# 1-Schematic_TL071.net
KiCad netlist of a schematic drawn in EasyEDA
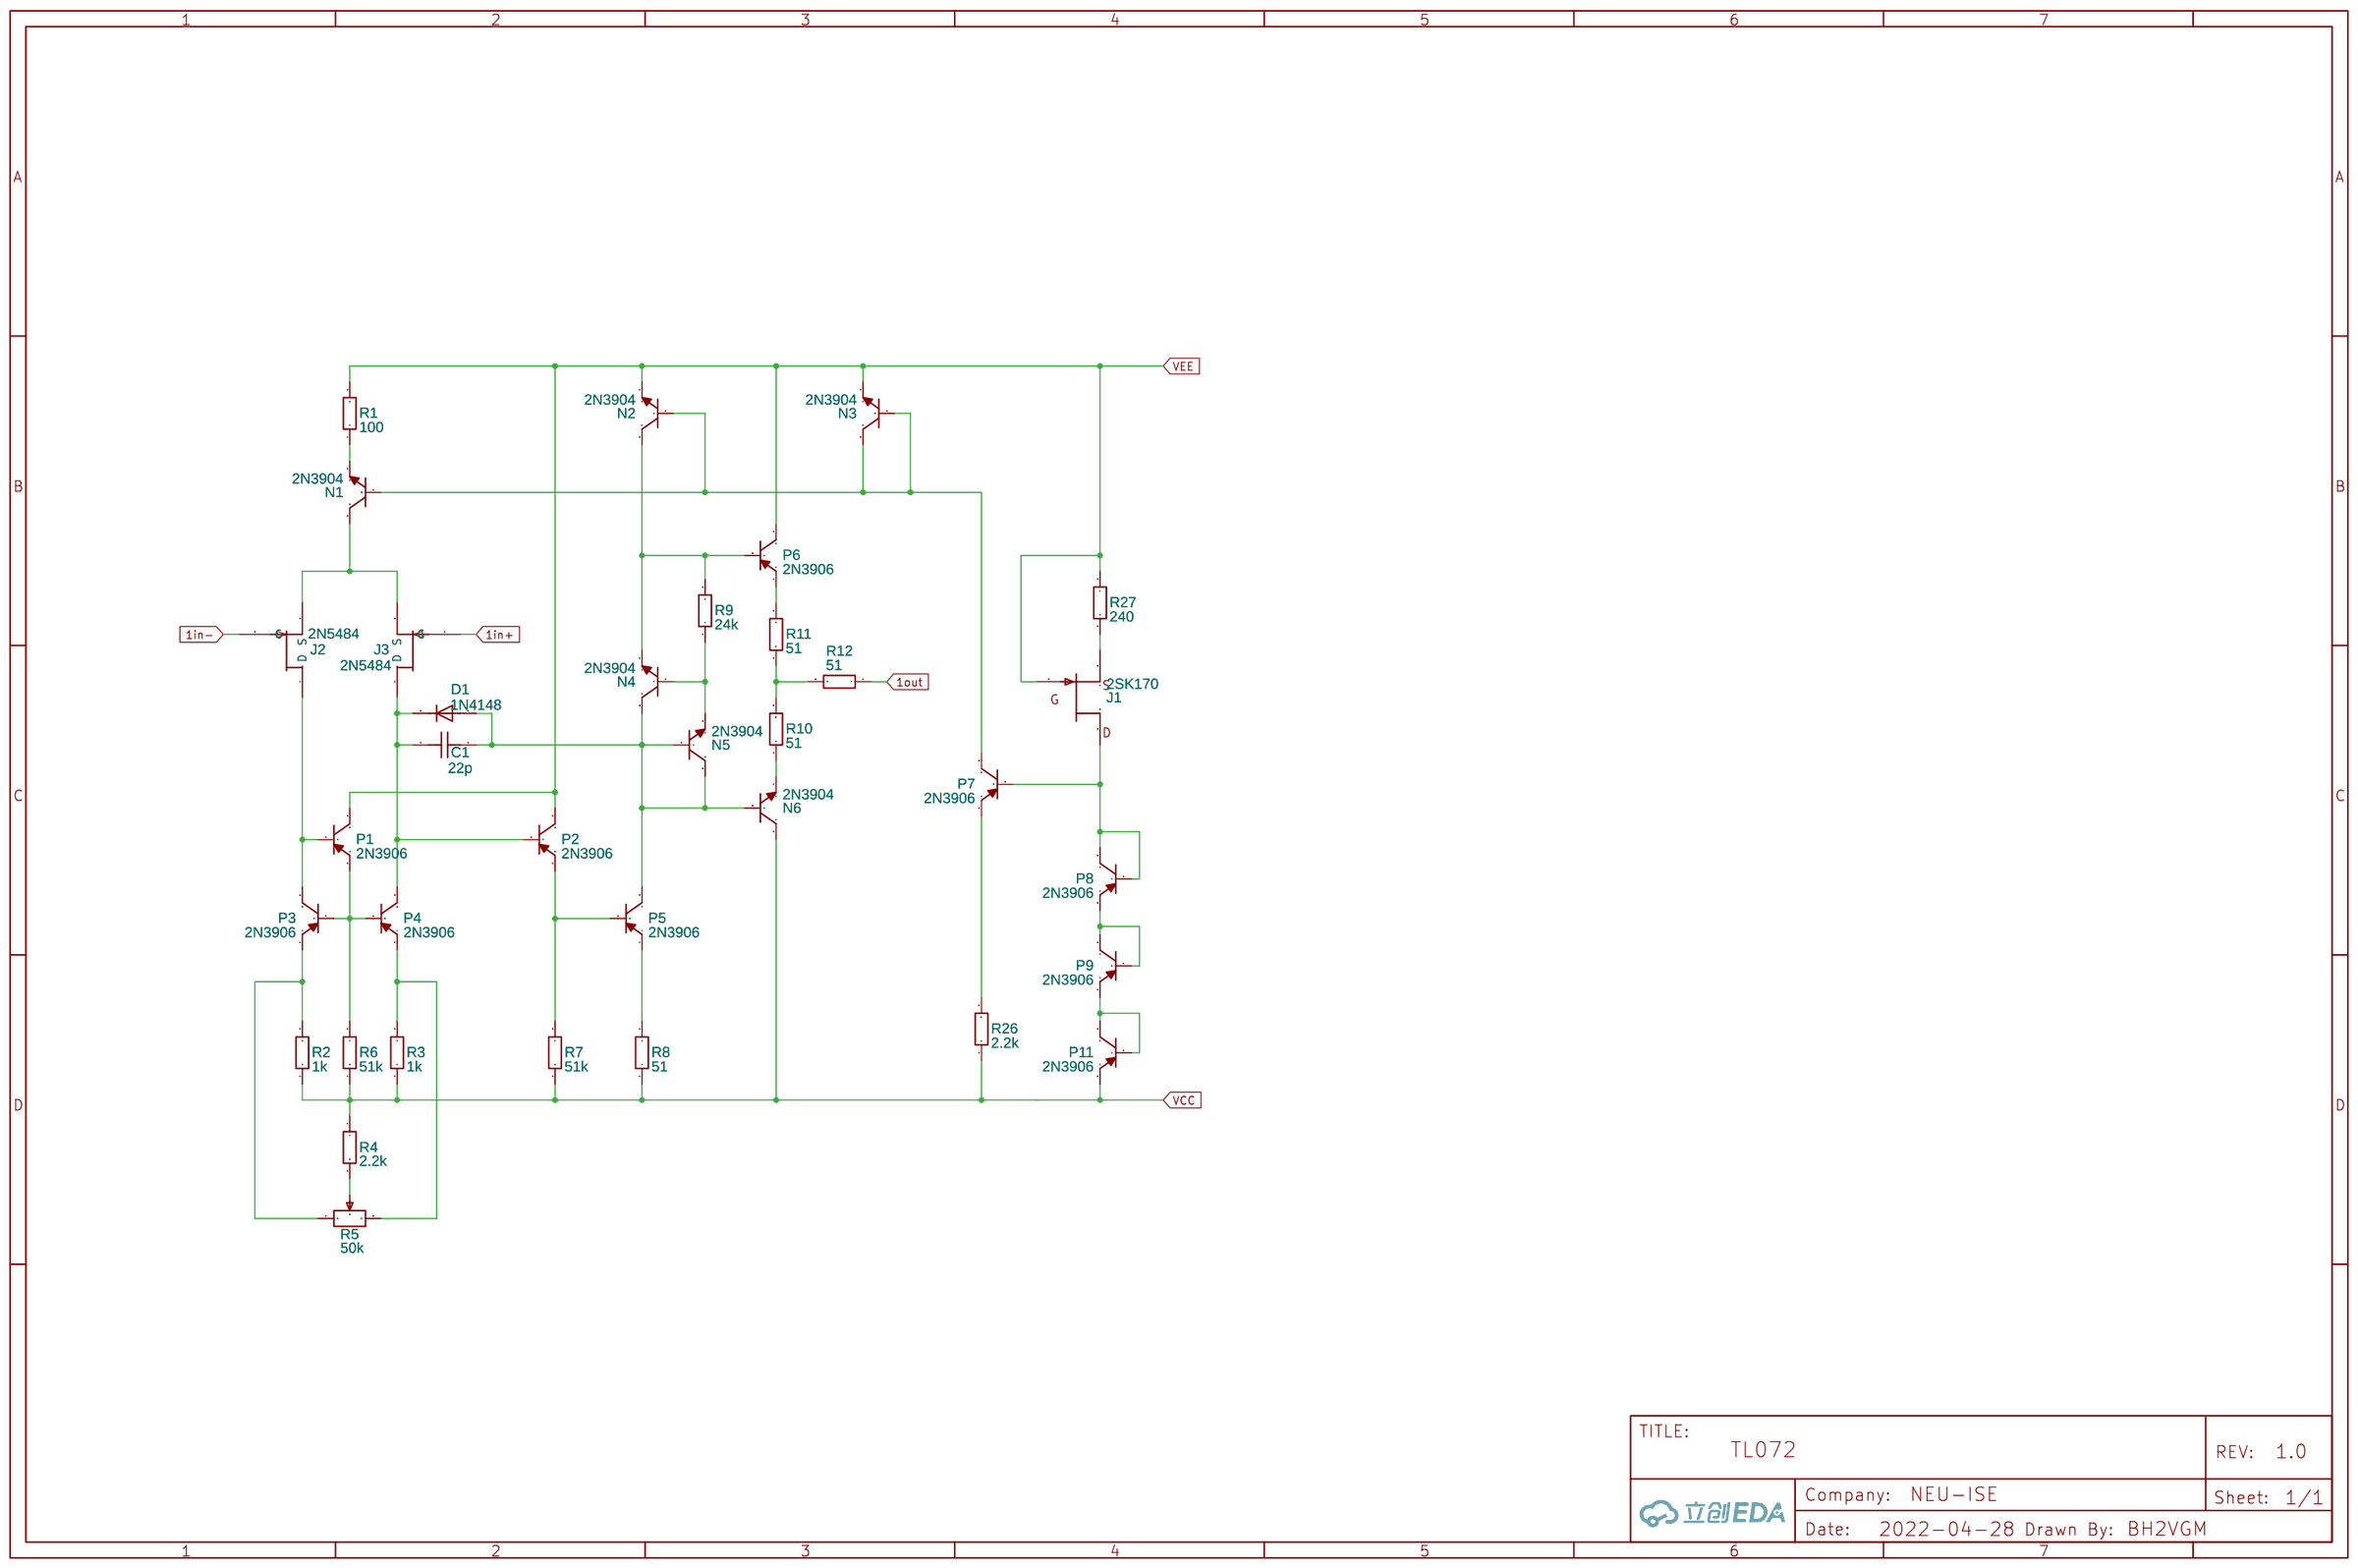
[diagram p0: schematic sheet]

(export (version "E")
  (design (tool "Eeschema 10.0.6"))
  (components
    (comp (ref "C1")
      (value "22p")
      (fields
        (field (name "BOM_Manufacturer Part") "C0805X7R103J500NT")
        (field (name "BOM_Supplier Part") "C2835540")
      )
      (libsource (lib "") (part "C0805X7R103J500NT"))
    )
    (comp (ref "D1") (value "1N4148") (libsource (lib "") (part "1N4148 DO-35")))
    (comp (ref "J1") (value "2SK170") (libsource (lib "") (part "2SK170")))
    (comp (ref "J2") (value "2N5484") (libsource (lib "") (part "2N5484")))
    (comp (ref "J3") (value "2N5484") (libsource (lib "") (part "2N5484_1")))
    (comp (ref "N1")
      (value "2N3904")
      (fields (field (name "BOM_Supplier Part") "C118538"))
      (libsource (lib "") (part "2N3904"))
    )
    (comp (ref "N2")
      (value "2N3904")
      (fields (field (name "BOM_Supplier Part") "C118538"))
      (libsource (lib "") (part "2N3904"))
    )
    (comp (ref "N3")
      (value "2N3904")
      (fields (field (name "BOM_Supplier Part") "C118538"))
      (libsource (lib "") (part "2N3904"))
    )
    (comp (ref "N4")
      (value "2N3904")
      (fields (field (name "BOM_Supplier Part") "C118538"))
      (libsource (lib "") (part "2N3904"))
    )
    (comp (ref "N5")
      (value "2N3904")
      (fields (field (name "BOM_Supplier Part") "C118538"))
      (libsource (lib "") (part "2N3904_1"))
    )
    (comp (ref "N6")
      (value "2N3904")
      (fields (field (name "BOM_Supplier Part") "C118538"))
      (libsource (lib "") (part "2N3904_1"))
    )
    (comp (ref "P1")
      (value "2N3906")
      (fields (field (name "BOM_Supplier Part") "C118539"))
      (libsource (lib "") (part "2N3906_C118539_1"))
    )
    (comp (ref "P2")
      (value "2N3906")
      (fields (field (name "BOM_Supplier Part") "C118539"))
      (libsource (lib "") (part "2N3906_C118539_1"))
    )
    (comp (ref "P3")
      (value "2N3906")
      (fields (field (name "BOM_Supplier Part") "C118539"))
      (libsource (lib "") (part "2N3906_C118539"))
    )
    (comp (ref "P4")
      (value "2N3906")
      (fields (field (name "BOM_Supplier Part") "C118539"))
      (libsource (lib "") (part "2N3906_C118539_1"))
    )
    (comp (ref "P5")
      (value "2N3906")
      (fields (field (name "BOM_Supplier Part") "C118539"))
      (libsource (lib "") (part "2N3906_C118539_1"))
    )
    (comp (ref "P6")
      (value "2N3906")
      (fields (field (name "BOM_Supplier Part") "C118539"))
      (libsource (lib "") (part "2N3906_C118539_1"))
    )
    (comp (ref "P7")
      (value "2N3906")
      (fields (field (name "BOM_Supplier Part") "C118539"))
      (libsource (lib "") (part "2N3906_C118539"))
    )
    (comp (ref "P8")
      (value "2N3906")
      (fields (field (name "BOM_Supplier Part") "C118539"))
      (libsource (lib "") (part "2N3906_C118539"))
    )
    (comp (ref "P9")
      (value "2N3906")
      (fields (field (name "BOM_Supplier Part") "C118539"))
      (libsource (lib "") (part "2N3906_C118539"))
    )
    (comp (ref "P11")
      (value "2N3906")
      (fields (field (name "BOM_Supplier Part") "C118539"))
      (libsource (lib "") (part "2N3906_C118539"))
    )
    (comp (ref "R1")
      (value "100")
      (fields (field (name "BOM_Manufacturer Part") "0805") (field (name "BOM_Supplier Part") "C9900012715"))
      (libsource (lib "") (part "0805_1"))
    )
    (comp (ref "R2")
      (value "1k")
      (fields (field (name "BOM_Manufacturer Part") "0805") (field (name "BOM_Supplier Part") "C9900012715"))
      (libsource (lib "") (part "0805_1"))
    )
    (comp (ref "R3")
      (value "1k")
      (fields (field (name "BOM_Manufacturer Part") "0805") (field (name "BOM_Supplier Part") "C9900012715"))
      (libsource (lib "") (part "0805_1"))
    )
    (comp (ref "R4")
      (value "2.2k")
      (fields (field (name "BOM_Manufacturer Part") "0805") (field (name "BOM_Supplier Part") "C9900012715"))
      (libsource (lib "") (part "0805_2"))
    )
    (comp (ref "R5")
      (value "50k")
      (fields
        (field (name "BOM_Manufacturer Part") "3296W-1-103LF")
        (field (name "BOM_Supplier Part") "C34846")
      )
      (libsource (lib "") (part "3296W"))
    )
    (comp (ref "R6")
      (value "51k")
      (fields (field (name "BOM_Manufacturer Part") "0805") (field (name "BOM_Supplier Part") "C9900012715"))
      (libsource (lib "") (part "0805_1"))
    )
    (comp (ref "R7")
      (value "51k")
      (fields (field (name "BOM_Manufacturer Part") "0805") (field (name "BOM_Supplier Part") "C9900012715"))
      (libsource (lib "") (part "0805_1"))
    )
    (comp (ref "R8")
      (value "51")
      (fields (field (name "BOM_Manufacturer Part") "0805") (field (name "BOM_Supplier Part") "C9900012715"))
      (libsource (lib "") (part "0805_1"))
    )
    (comp (ref "R9")
      (value "24k")
      (fields (field (name "BOM_Manufacturer Part") "0805") (field (name "BOM_Supplier Part") "C9900012715"))
      (libsource (lib "") (part "0805_1"))
    )
    (comp (ref "R10")
      (value "51")
      (fields (field (name "BOM_Manufacturer Part") "0805") (field (name "BOM_Supplier Part") "C9900012715"))
      (libsource (lib "") (part "0805_1"))
    )
    (comp (ref "R11")
      (value "51")
      (fields (field (name "BOM_Manufacturer Part") "0805") (field (name "BOM_Supplier Part") "C9900012715"))
      (libsource (lib "") (part "0805_1"))
    )
    (comp (ref "R12")
      (value "51")
      (fields (field (name "BOM_Manufacturer Part") "0805") (field (name "BOM_Supplier Part") "C9900012715"))
      (libsource (lib "") (part "0805"))
    )
    (comp (ref "R26")
      (value "2.2k")
      (fields (field (name "BOM_Manufacturer Part") "0805") (field (name "BOM_Supplier Part") "C9900012715"))
      (libsource (lib "") (part "0805_1"))
    )
    (comp (ref "R27")
      (value "240")
      (fields (field (name "BOM_Manufacturer Part") "0805") (field (name "BOM_Supplier Part") "C9900012715"))
      (libsource (lib "") (part "0805_2"))
    )
  )
  (nets
    (net (code "1") (name "1in+") (class "Default")
      (node (ref "J3") (pin "3") (pinfunction "G_3") (pintype "unspecified"))
    )
    (net (code "2") (name "1in-") (class "Default")
      (node (ref "J2") (pin "3") (pinfunction "G_3") (pintype "unspecified"))
    )
    (net (code "3") (name "1out") (class "Default")
      (node (ref "R12") (pin "1") (pinfunction "1_1") (pintype "unspecified"))
    )
    (net (code "4") (name "Net-(J1-D)") (class "Default")
      (node (ref "J1") (pin "3") (pinfunction "D_3") (pintype "unspecified"))
      (node (ref "P7") (pin "2") (pinfunction "2_2") (pintype "input"))
      (node (ref "P8") (pin "2") (pinfunction "2_2") (pintype "input"))
      (node (ref "P8") (pin "3") (pinfunction "3_3") (pintype "input"))
    )
    (net (code "5") (name "Net-(J1-S)") (class "Default")
      (node (ref "J1") (pin "1") (pinfunction "S_1") (pintype "unspecified"))
      (node (ref "R27") (pin "2") (pinfunction "2_2") (pintype "unspecified"))
    )
    (net (code "6") (name "Net-(J2-D)") (class "Default")
      (node (ref "J2") (pin "1") (pinfunction "D_1") (pintype "unspecified"))
      (node (ref "P1") (pin "2") (pinfunction "2_2") (pintype "input"))
      (node (ref "P3") (pin "3") (pinfunction "3_3") (pintype "input"))
    )
    (net (code "7") (name "Net-(J2-S)") (class "Default")
      (node (ref "J2") (pin "2") (pinfunction "S_2") (pintype "unspecified"))
      (node (ref "J3") (pin "2") (pinfunction "S_2") (pintype "unspecified"))
      (node (ref "N1") (pin "3") (pinfunction "C_3") (pintype "unspecified"))
    )
    (net (code "8") (name "Net-(J3-D)") (class "Default")
      (node (ref "C1") (pin "1") (pinfunction "1_1") (pintype "unspecified"))
      (node (ref "D1") (pin "2") (pinfunction "2_2") (pintype "unspecified"))
      (node (ref "J3") (pin "1") (pinfunction "D_1") (pintype "unspecified"))
      (node (ref "P2") (pin "2") (pinfunction "2_2") (pintype "input"))
      (node (ref "P4") (pin "3") (pinfunction "3_3") (pintype "input"))
    )
    (net (code "9") (name "Net-(N1-B)") (class "Default")
      (node (ref "N1") (pin "2") (pinfunction "B_2") (pintype "unspecified"))
      (node (ref "N2") (pin "2") (pinfunction "B_2") (pintype "unspecified"))
      (node (ref "N3") (pin "2") (pinfunction "B_2") (pintype "unspecified"))
      (node (ref "N3") (pin "3") (pinfunction "C_3") (pintype "unspecified"))
      (node (ref "P7") (pin "3") (pinfunction "3_3") (pintype "input"))
    )
    (net (code "10") (name "Net-(N1-E)") (class "Default")
      (node (ref "N1") (pin "1") (pinfunction "E_1") (pintype "unspecified"))
      (node (ref "R1") (pin "1") (pinfunction "1_1") (pintype "unspecified"))
    )
    (net (code "11") (name "Net-(N2-C)") (class "Default")
      (node (ref "N2") (pin "3") (pinfunction "C_3") (pintype "unspecified"))
      (node (ref "N4") (pin "1") (pinfunction "E_1") (pintype "unspecified"))
      (node (ref "P6") (pin "2") (pinfunction "2_2") (pintype "input"))
      (node (ref "R9") (pin "2") (pinfunction "2_2") (pintype "unspecified"))
    )
    (net (code "12") (name "Net-(N4-B)") (class "Default")
      (node (ref "N4") (pin "2") (pinfunction "B_2") (pintype "unspecified"))
      (node (ref "N5") (pin "1") (pinfunction "E_1") (pintype "unspecified"))
      (node (ref "R9") (pin "1") (pinfunction "1_1") (pintype "unspecified"))
    )
    (net (code "13") (name "Net-(N4-C)") (class "Default")
      (node (ref "C1") (pin "2") (pinfunction "2_2") (pintype "unspecified"))
      (node (ref "D1") (pin "1") (pinfunction "1_1") (pintype "unspecified"))
      (node (ref "N4") (pin "3") (pinfunction "C_3") (pintype "unspecified"))
      (node (ref "N5") (pin "2") (pinfunction "B_2") (pintype "unspecified"))
      (node (ref "N5") (pin "3") (pinfunction "C_3") (pintype "unspecified"))
      (node (ref "N6") (pin "2") (pinfunction "B_2") (pintype "unspecified"))
      (node (ref "P5") (pin "3") (pinfunction "3_3") (pintype "input"))
    )
    (net (code "14") (name "Net-(N6-E)") (class "Default")
      (node (ref "N6") (pin "1") (pinfunction "E_1") (pintype "unspecified"))
      (node (ref "R10") (pin "1") (pinfunction "1_1") (pintype "unspecified"))
    )
    (net (code "15") (name "Net-(P1-Pad1)") (class "Default")
      (node (ref "P1") (pin "1") (pinfunction "1_1") (pintype "input"))
      (node (ref "P3") (pin "2") (pinfunction "2_2") (pintype "input"))
      (node (ref "P4") (pin "2") (pinfunction "2_2") (pintype "input"))
      (node (ref "R6") (pin "2") (pinfunction "2_2") (pintype "unspecified"))
    )
    (net (code "16") (name "Net-(P2-Pad1)") (class "Default")
      (node (ref "P2") (pin "1") (pinfunction "1_1") (pintype "input"))
      (node (ref "P5") (pin "2") (pinfunction "2_2") (pintype "input"))
      (node (ref "R7") (pin "2") (pinfunction "2_2") (pintype "unspecified"))
    )
    (net (code "17") (name "Net-(P3-Pad1)") (class "Default")
      (node (ref "P3") (pin "1") (pinfunction "1_1") (pintype "input"))
      (node (ref "R2") (pin "2") (pinfunction "2_2") (pintype "unspecified"))
      (node (ref "R5") (pin "3") (pinfunction "3_3") (pintype "input"))
    )
    (net (code "18") (name "Net-(P4-Pad1)") (class "Default")
      (node (ref "P4") (pin "1") (pinfunction "1_1") (pintype "input"))
      (node (ref "R3") (pin "2") (pinfunction "2_2") (pintype "unspecified"))
      (node (ref "R5") (pin "1") (pinfunction "1_1") (pintype "input"))
    )
    (net (code "19") (name "Net-(P5-Pad1)") (class "Default")
      (node (ref "P5") (pin "1") (pinfunction "1_1") (pintype "input"))
      (node (ref "R8") (pin "2") (pinfunction "2_2") (pintype "unspecified"))
    )
    (net (code "20") (name "Net-(P6-Pad1)") (class "Default")
      (node (ref "P6") (pin "1") (pinfunction "1_1") (pintype "input"))
      (node (ref "R11") (pin "2") (pinfunction "2_2") (pintype "unspecified"))
    )
    (net (code "21") (name "Net-(P7-Pad1)") (class "Default")
      (node (ref "P7") (pin "1") (pinfunction "1_1") (pintype "input"))
      (node (ref "R26") (pin "2") (pinfunction "2_2") (pintype "unspecified"))
    )
    (net (code "22") (name "Net-(P8-Pad1)") (class "Default")
      (node (ref "P8") (pin "1") (pinfunction "1_1") (pintype "input"))
      (node (ref "P9") (pin "2") (pinfunction "2_2") (pintype "input"))
      (node (ref "P9") (pin "3") (pinfunction "3_3") (pintype "input"))
    )
    (net (code "23") (name "Net-(P11-Pad2)") (class "Default")
      (node (ref "P11") (pin "2") (pinfunction "2_2") (pintype "input"))
      (node (ref "P11") (pin "3") (pinfunction "3_3") (pintype "input"))
      (node (ref "P9") (pin "1") (pinfunction "1_1") (pintype "input"))
    )
    (net (code "24") (name "Net-(R4-Pad2)") (class "Default")
      (node (ref "R4") (pin "2") (pinfunction "2_2") (pintype "unspecified"))
      (node (ref "R5") (pin "2") (pinfunction "2_2") (pintype "input"))
    )
    (net (code "25") (name "Net-(R10-Pad2)") (class "Default")
      (node (ref "R10") (pin "2") (pinfunction "2_2") (pintype "unspecified"))
      (node (ref "R11") (pin "1") (pinfunction "1_1") (pintype "unspecified"))
      (node (ref "R12") (pin "2") (pinfunction "2_2") (pintype "unspecified"))
    )
    (net (code "26") (name "VCC") (class "Default")
      (node (ref "N6") (pin "3") (pinfunction "C_3") (pintype "unspecified"))
      (node (ref "P11") (pin "1") (pinfunction "1_1") (pintype "input"))
      (node (ref "R2") (pin "1") (pinfunction "1_1") (pintype "unspecified"))
      (node (ref "R26") (pin "1") (pinfunction "1_1") (pintype "unspecified"))
      (node (ref "R3") (pin "1") (pinfunction "1_1") (pintype "unspecified"))
      (node (ref "R4") (pin "1") (pinfunction "1_1") (pintype "unspecified"))
      (node (ref "R6") (pin "1") (pinfunction "1_1") (pintype "unspecified"))
      (node (ref "R7") (pin "1") (pinfunction "1_1") (pintype "unspecified"))
      (node (ref "R8") (pin "1") (pinfunction "1_1") (pintype "unspecified"))
    )
    (net (code "27") (name "VEE") (class "Default")
      (node (ref "J1") (pin "2") (pinfunction "G_2") (pintype "unspecified"))
      (node (ref "N2") (pin "1") (pinfunction "E_1") (pintype "unspecified"))
      (node (ref "N3") (pin "1") (pinfunction "E_1") (pintype "unspecified"))
      (node (ref "P1") (pin "3") (pinfunction "3_3") (pintype "input"))
      (node (ref "P2") (pin "3") (pinfunction "3_3") (pintype "input"))
      (node (ref "P6") (pin "3") (pinfunction "3_3") (pintype "input"))
      (node (ref "R1") (pin "2") (pinfunction "2_2") (pintype "unspecified"))
      (node (ref "R27") (pin "1") (pinfunction "1_1") (pintype "unspecified"))
    )
  )
)
